# rfid.net
KiCad netlist of a schematic drawn in EAGLE
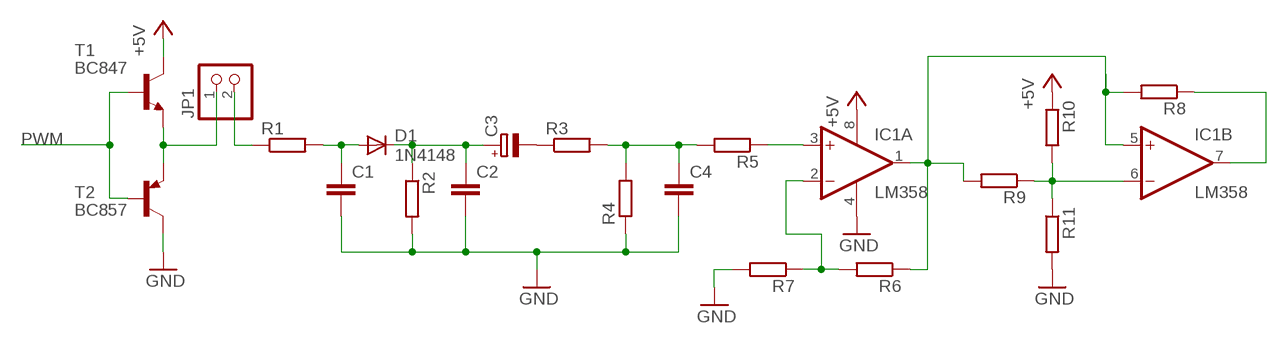
[diagram p0: schematic, sheet 1]

(export (version "E")
  (design (tool "Eeschema 10.0.6"))
  (components
    (comp (ref "C1")
      (value "C-EUC0805K")
      (footprint "eagle-import:C0805K")
      (libsource (lib "eagle-import") (part "C-EUC0805K"))
    )
    (comp (ref "C2")
      (value "C-EUC0805K")
      (footprint "eagle-import:C0805K")
      (libsource (lib "eagle-import") (part "C-EUC0805K"))
    )
    (comp (ref "C3")
      (value "CPOL-EU")
      (footprint "eagle-import:SMC_A")
      (libsource (lib "eagle-import") (part "CPOL-EU"))
    )
    (comp (ref "C4")
      (value "C-EUC0805K")
      (footprint "eagle-import:C0805K")
      (libsource (lib "eagle-import") (part "C-EUC0805K"))
    )
    (comp (ref "D1")
      (value "1N4148")
      (footprint "eagle-import:D0805")
      (libsource (lib "eagle-import") (part "1N4148"))
    )
    (comp (ref "IC1")
      (value "LM358")
      (footprint "eagle-import:SO08")
      (libsource (lib "eagle-import") (part "LM358"))
    )
    (comp (ref "JP1")
      (value "PINHD-1X2")
      (footprint "eagle-import:1X02")
      (libsource (lib "eagle-import") (part "PINHD-1X2"))
    )
    (comp (ref "R1")
      (value "R-EU_R0805")
      (footprint "eagle-import:R0805")
      (libsource (lib "eagle-import") (part "R-EU_R0805"))
    )
    (comp (ref "R2")
      (value "R-EU_R0805")
      (footprint "eagle-import:R0805")
      (libsource (lib "eagle-import") (part "R-EU_R0805"))
    )
    (comp (ref "R3")
      (value "R-EU_R0805")
      (footprint "eagle-import:R0805")
      (libsource (lib "eagle-import") (part "R-EU_R0805"))
    )
    (comp (ref "R4")
      (value "R-EU_R0805")
      (footprint "eagle-import:R0805")
      (libsource (lib "eagle-import") (part "R-EU_R0805"))
    )
    (comp (ref "R5")
      (value "R-EU_R0805")
      (footprint "eagle-import:R0805")
      (libsource (lib "eagle-import") (part "R-EU_R0805"))
    )
    (comp (ref "R6")
      (value "R-EU_R0805")
      (footprint "eagle-import:R0805")
      (libsource (lib "eagle-import") (part "R-EU_R0805"))
    )
    (comp (ref "R7")
      (value "R-EU_R0805")
      (footprint "eagle-import:R0805")
      (libsource (lib "eagle-import") (part "R-EU_R0805"))
    )
    (comp (ref "R8")
      (value "R-EU_R0805")
      (footprint "eagle-import:R0805")
      (libsource (lib "eagle-import") (part "R-EU_R0805"))
    )
    (comp (ref "R9")
      (value "R-EU_R0805")
      (footprint "eagle-import:R0805")
      (libsource (lib "eagle-import") (part "R-EU_R0805"))
    )
    (comp (ref "R10")
      (value "R-EU_R0805")
      (footprint "eagle-import:R0805")
      (libsource (lib "eagle-import") (part "R-EU_R0805"))
    )
    (comp (ref "R11")
      (value "R-EU_R0805")
      (footprint "eagle-import:R0805")
      (libsource (lib "eagle-import") (part "R-EU_R0805"))
    )
    (comp (ref "T1")
      (value "BC847")
      (footprint "eagle-import:SOT23")
      (libsource (lib "eagle-import") (part "BC847"))
    )
    (comp (ref "T2")
      (value "BC857")
      (footprint "eagle-import:SOT23-BEC")
      (libsource (lib "eagle-import") (part "BC857"))
    )
  )
  (nets
    (net (code "1") (name "+5V") (class "Default")
      (node (ref "IC1") (pin "8") (pinfunction "V+_8") (pintype "power_in"))
      (node (ref "R10") (pin "1") (pinfunction "1_1") (pintype "passive"))
      (node (ref "T1") (pin "3") (pinfunction "C_3") (pintype "passive"))
    )
    (net (code "2") (name "/PWM") (class "Default")
      (node (ref "T1") (pin "1") (pinfunction "B_1") (pintype "passive"))
      (node (ref "T2") (pin "B") (pinfunction "B_B") (pintype "passive"))
    )
    (net (code "3") (name "GND") (class "Default")
      (node (ref "C1") (pin "2") (pinfunction "2_2") (pintype "passive"))
      (node (ref "C2") (pin "2") (pinfunction "2_2") (pintype "passive"))
      (node (ref "C4") (pin "2") (pinfunction "2_2") (pintype "passive"))
      (node (ref "IC1") (pin "4") (pinfunction "V-_4") (pintype "power_in"))
      (node (ref "R11") (pin "2") (pinfunction "2_2") (pintype "passive"))
      (node (ref "R2") (pin "2") (pinfunction "2_2") (pintype "passive"))
      (node (ref "R4") (pin "1") (pinfunction "1_1") (pintype "passive"))
      (node (ref "R7") (pin "2") (pinfunction "2_2") (pintype "passive"))
      (node (ref "T2") (pin "C") (pinfunction "C_C") (pintype "passive"))
    )
    (net (code "4") (name "Net-(C1-Pad1)") (class "Default")
      (node (ref "C1") (pin "1") (pinfunction "1_1") (pintype "passive"))
      (node (ref "D1") (pin "A") (pinfunction "A_A") (pintype "passive"))
      (node (ref "R1") (pin "2") (pinfunction "2_2") (pintype "passive"))
    )
    (net (code "5") (name "Net-(C2-Pad1)") (class "Default")
      (node (ref "C2") (pin "1") (pinfunction "1_1") (pintype "passive"))
      (node (ref "C3") (pin "+") (pinfunction "+_+") (pintype "passive"))
      (node (ref "D1") (pin "C") (pinfunction "C_C") (pintype "passive"))
      (node (ref "R2") (pin "1") (pinfunction "1_1") (pintype "passive"))
    )
    (net (code "6") (name "Net-(C3-Pad-)") (class "Default")
      (node (ref "C3") (pin "-") (pinfunction "-_-") (pintype "passive"))
      (node (ref "R3") (pin "1") (pinfunction "1_1") (pintype "passive"))
    )
    (net (code "7") (name "Net-(C4-Pad1)") (class "Default")
      (node (ref "C4") (pin "1") (pinfunction "1_1") (pintype "passive"))
      (node (ref "R3") (pin "2") (pinfunction "2_2") (pintype "passive"))
      (node (ref "R4") (pin "2") (pinfunction "2_2") (pintype "passive"))
      (node (ref "R5") (pin "2") (pinfunction "2_2") (pintype "passive"))
    )
    (net (code "8") (name "Net-(IC1A-+IN)") (class "Default")
      (node (ref "IC1") (pin "3") (pinfunction "+IN_3") (pintype "input"))
      (node (ref "R5") (pin "1") (pinfunction "1_1") (pintype "passive"))
    )
    (net (code "9") (name "Net-(IC1A--IN)") (class "Default")
      (node (ref "IC1") (pin "2") (pinfunction "-IN_2") (pintype "input"))
      (node (ref "R6") (pin "2") (pinfunction "2_2") (pintype "passive"))
      (node (ref "R7") (pin "1") (pinfunction "1_1") (pintype "passive"))
    )
    (net (code "10") (name "Net-(IC1A-OUT)") (class "Default")
      (node (ref "IC1") (pin "1") (pinfunction "OUT_1") (pintype "output"))
      (node (ref "IC1") (pin "5") (pinfunction "+IN_5") (pintype "input"))
      (node (ref "R6") (pin "1") (pinfunction "1_1") (pintype "passive"))
      (node (ref "R8") (pin "2") (pinfunction "2_2") (pintype "passive"))
      (node (ref "R9") (pin "2") (pinfunction "2_2") (pintype "passive"))
    )
    (net (code "11") (name "Net-(IC1B--IN)") (class "Default")
      (node (ref "IC1") (pin "6") (pinfunction "-IN_6") (pintype "input"))
      (node (ref "R10") (pin "2") (pinfunction "2_2") (pintype "passive"))
      (node (ref "R11") (pin "1") (pinfunction "1_1") (pintype "passive"))
      (node (ref "R9") (pin "1") (pinfunction "1_1") (pintype "passive"))
    )
    (net (code "12") (name "Net-(IC1B-OUT)") (class "Default")
      (node (ref "IC1") (pin "7") (pinfunction "OUT_7") (pintype "output"))
      (node (ref "R8") (pin "1") (pinfunction "1_1") (pintype "passive"))
    )
    (net (code "13") (name "Net-(JP1-Pad2)") (class "Default")
      (node (ref "JP1") (pin "2") (pinfunction "2_2") (pintype "passive"))
      (node (ref "R1") (pin "1") (pinfunction "1_1") (pintype "passive"))
    )
    (net (code "14") (name "Net-(T1-E)") (class "Default")
      (node (ref "JP1") (pin "1") (pinfunction "1_1") (pintype "passive"))
      (node (ref "T1") (pin "2") (pinfunction "E_2") (pintype "passive"))
      (node (ref "T2") (pin "E") (pinfunction "E_E") (pintype "passive"))
    )
  )
)
